# 3_Motor_Drives.net
KiCad netlist of a schematic drawn in Altium Designer
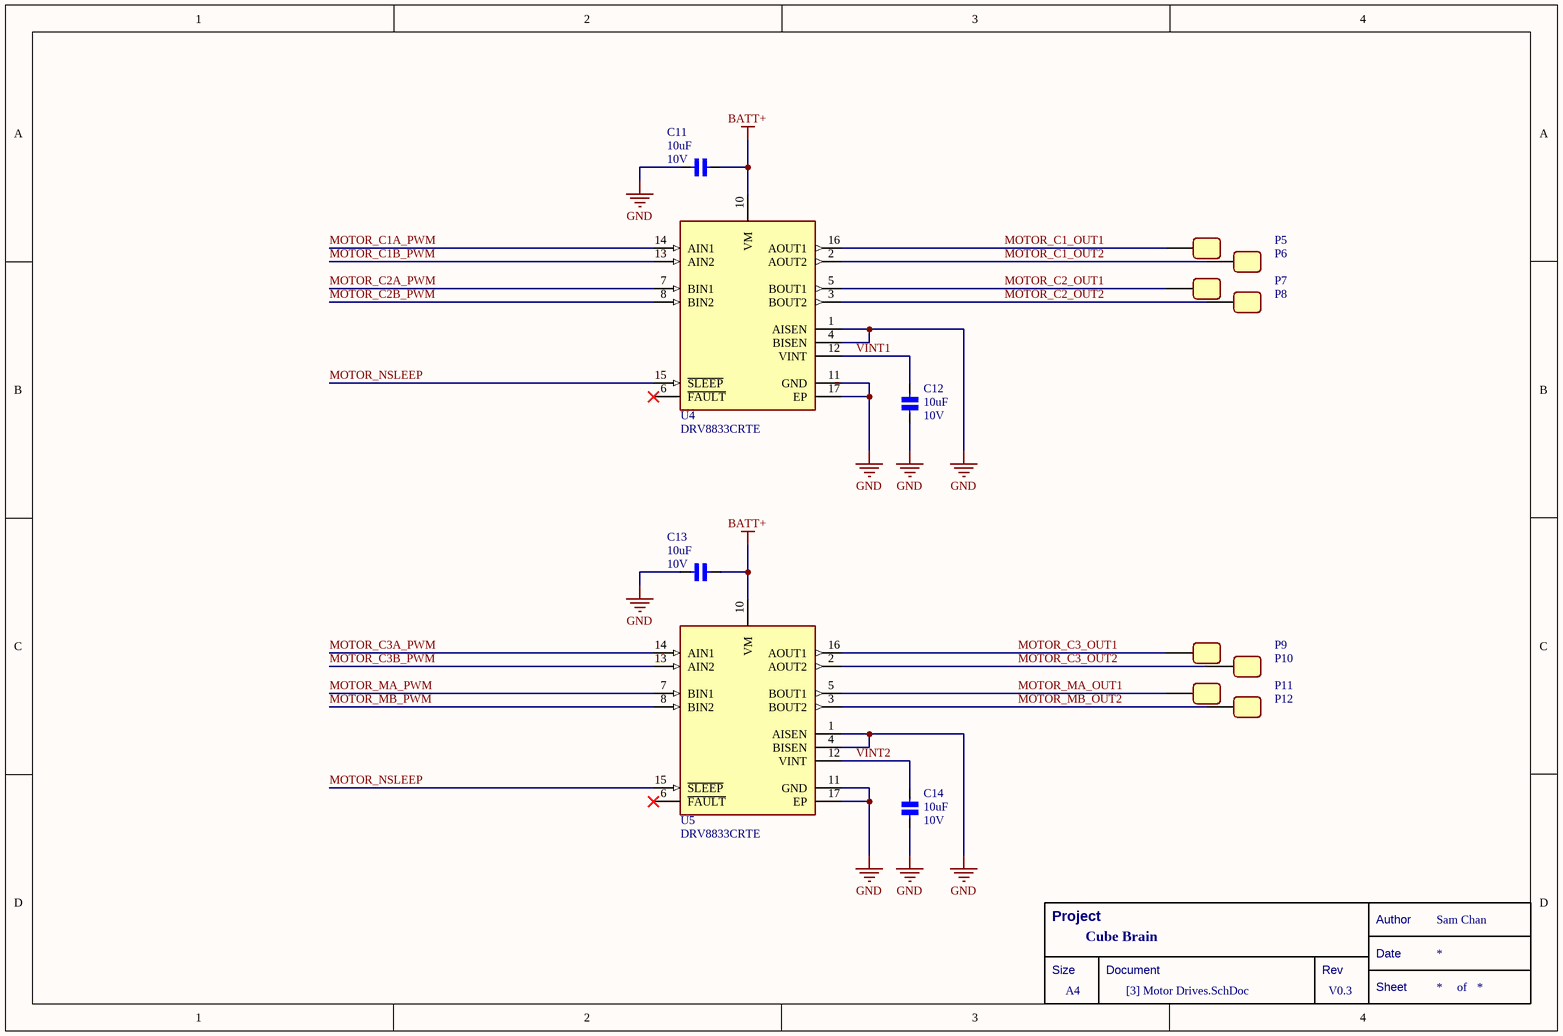
[diagram p0: [3] Motor Drives.SchDoc]

(export (version "E")
  (design (tool "Eeschema 10.0.6"))
  (components
    (comp (ref "C11")
      (value "10uF")
      (footprint "CAPC0402X05N")
      (description "CAP CER 10UF 10V X5R 0402")
      (fields
        (field (name "MANUFACTURER") "Murata Electronics")
        (field (name "MANUFACTURER PART NUMBER") "GRM155R61A106ME44D")
        (field (name "CAPACITANCE") "10uF")
        (field (name "VOLTAGE - RATED") "10V")
      )
      (libsource (lib "") (part "CER 10UF 10V_1"))
    )
    (comp (ref "C12")
      (value "10uF")
      (footprint "CAPC0402X05N")
      (description "CAP CER 10UF 10V X5R 0402")
      (fields
        (field (name "MANUFACTURER") "Murata Electronics")
        (field (name "MANUFACTURER PART NUMBER") "GRM155R61A106ME44D")
        (field (name "CAPACITANCE") "10uF")
        (field (name "VOLTAGE - RATED") "10V")
      )
      (libsource (lib "Cube Library") (part "CER 10UF 10V"))
    )
    (comp (ref "C13")
      (value "10uF")
      (footprint "CAPC0402X05N")
      (description "CAP CER 10UF 10V X5R 0402")
      (fields
        (field (name "MANUFACTURER") "Murata Electronics")
        (field (name "MANUFACTURER PART NUMBER") "GRM155R61A106ME44D")
        (field (name "CAPACITANCE") "10uF")
        (field (name "VOLTAGE - RATED") "10V")
      )
      (libsource (lib "") (part "CER 10UF 10V_1"))
    )
    (comp (ref "C14")
      (value "10uF")
      (footprint "CAPC0402X05N")
      (description "CAP CER 10UF 10V X5R 0402")
      (fields
        (field (name "MANUFACTURER") "Murata Electronics")
        (field (name "MANUFACTURER PART NUMBER") "GRM155R61A106ME44D")
        (field (name "CAPACITANCE") "10uF")
        (field (name "VOLTAGE - RATED") "10V")
      )
      (libsource (lib "Cube Library") (part "CER 10UF 10V"))
    )
    (comp (ref "P5")
      (value "PAD_1")
      (footprint "PAD_1.0X1.5MM")
      (description "a Rec Pad, 1.0X1.5mm")
      (libsource (lib "Cube Library") (part "PAD_1"))
    )
    (comp (ref "P6")
      (value "PAD_1")
      (footprint "PAD_1.0X1.5MM")
      (description "a Rec Pad, 1.0X1.5mm")
      (libsource (lib "Cube Library") (part "PAD_1"))
    )
    (comp (ref "P7")
      (value "PAD_1")
      (footprint "PAD_1.0X1.5MM")
      (description "a Rec Pad, 1.0X1.5mm")
      (libsource (lib "Cube Library") (part "PAD_1"))
    )
    (comp (ref "P8")
      (value "PAD_1")
      (footprint "PAD_1.0X1.5MM")
      (description "a Rec Pad, 1.0X1.5mm")
      (libsource (lib "Cube Library") (part "PAD_1"))
    )
    (comp (ref "P9")
      (value "PAD_1")
      (footprint "PAD_1.0X1.5MM")
      (description "a Rec Pad, 1.0X1.5mm")
      (libsource (lib "Cube Library") (part "PAD_1"))
    )
    (comp (ref "P10")
      (value "PAD_1")
      (footprint "PAD_1.0X1.5MM")
      (description "a Rec Pad, 1.0X1.5mm")
      (libsource (lib "Cube Library") (part "PAD_1"))
    )
    (comp (ref "P11")
      (value "PAD_1")
      (footprint "PAD_1.0X1.5MM")
      (description "a Rec Pad, 1.0X1.5mm")
      (libsource (lib "Cube Library") (part "PAD_1"))
    )
    (comp (ref "P12")
      (value "PAD_1")
      (footprint "PAD_1.0X1.5MM")
      (description "a Rec Pad, 1.0X1.5mm")
      (libsource (lib "Cube Library") (part "PAD_1"))
    )
    (comp (ref "U4")
      (value "DRV8833CRTE")
      (footprint "DRV8833CRTER")
      (description "Bipolar Motor Driver Power MOSFET PWM 16-WQFN (3x3)")
      (fields (field (name "MANUFACTURER") "Texas Instruments"))
      (libsource (lib "Cube Library") (part "DRV8833CRTE"))
    )
    (comp (ref "U5")
      (value "DRV8833CRTE")
      (footprint "DRV8833CRTER")
      (description "Bipolar Motor Driver Power MOSFET PWM 16-WQFN (3x3)")
      (fields (field (name "MANUFACTURER") "Texas Instruments"))
      (libsource (lib "Cube Library") (part "DRV8833CRTE"))
    )
  )
  (nets
    (net (code "1") (name "/MOTOR_C1A_PWM") (class "Default")
      (node (ref "U4") (pin "14") (pinfunction "AIN1_14") (pintype "input"))
    )
    (net (code "2") (name "/MOTOR_C1B_PWM") (class "Default")
      (node (ref "U4") (pin "13") (pinfunction "AIN2_13") (pintype "input"))
    )
    (net (code "3") (name "/MOTOR_C1_OUT1") (class "Default")
      (node (ref "P5") (pin "1") (pinfunction "1_1") (pintype "passive"))
      (node (ref "U4") (pin "16") (pinfunction "AOUT1_16") (pintype "output"))
    )
    (net (code "4") (name "/MOTOR_C1_OUT2") (class "Default")
      (node (ref "P6") (pin "1") (pinfunction "1_1") (pintype "passive"))
      (node (ref "U4") (pin "2") (pinfunction "AOUT2_2") (pintype "output"))
    )
    (net (code "5") (name "/MOTOR_C2A_PWM") (class "Default")
      (node (ref "U4") (pin "7") (pinfunction "BIN1_7") (pintype "input"))
    )
    (net (code "6") (name "/MOTOR_C2B_PWM") (class "Default")
      (node (ref "U4") (pin "8") (pinfunction "BIN2_8") (pintype "input"))
    )
    (net (code "7") (name "/MOTOR_C2_OUT1") (class "Default")
      (node (ref "P7") (pin "1") (pinfunction "1_1") (pintype "passive"))
      (node (ref "U4") (pin "5") (pinfunction "BOUT1_5") (pintype "output"))
    )
    (net (code "8") (name "/MOTOR_C2_OUT2") (class "Default")
      (node (ref "P8") (pin "1") (pinfunction "1_1") (pintype "passive"))
      (node (ref "U4") (pin "3") (pinfunction "BOUT2_3") (pintype "output"))
    )
    (net (code "9") (name "/MOTOR_C3A_PWM") (class "Default")
      (node (ref "U5") (pin "14") (pinfunction "AIN1_14") (pintype "input"))
    )
    (net (code "10") (name "/MOTOR_C3B_PWM") (class "Default")
      (node (ref "U5") (pin "13") (pinfunction "AIN2_13") (pintype "input"))
    )
    (net (code "11") (name "/MOTOR_C3_OUT1") (class "Default")
      (node (ref "P9") (pin "1") (pinfunction "1_1") (pintype "passive"))
      (node (ref "U5") (pin "16") (pinfunction "AOUT1_16") (pintype "output"))
    )
    (net (code "12") (name "/MOTOR_C3_OUT2") (class "Default")
      (node (ref "P10") (pin "1") (pinfunction "1_1") (pintype "passive"))
      (node (ref "U5") (pin "2") (pinfunction "AOUT2_2") (pintype "output"))
    )
    (net (code "13") (name "/MOTOR_MA_OUT1") (class "Default")
      (node (ref "P11") (pin "1") (pinfunction "1_1") (pintype "passive"))
      (node (ref "U5") (pin "5") (pinfunction "BOUT1_5") (pintype "output"))
    )
    (net (code "14") (name "/MOTOR_MA_PWM") (class "Default")
      (node (ref "U5") (pin "7") (pinfunction "BIN1_7") (pintype "input"))
    )
    (net (code "15") (name "/MOTOR_MB_OUT2") (class "Default")
      (node (ref "P12") (pin "1") (pinfunction "1_1") (pintype "passive"))
      (node (ref "U5") (pin "3") (pinfunction "BOUT2_3") (pintype "output"))
    )
    (net (code "16") (name "/MOTOR_MB_PWM") (class "Default")
      (node (ref "U5") (pin "8") (pinfunction "BIN2_8") (pintype "input"))
    )
    (net (code "17") (name "/MOTOR_NSLEEP") (class "Default")
      (node (ref "U4") (pin "15") (pinfunction "~{SLEEP}_15") (pintype "input"))
      (node (ref "U5") (pin "15") (pinfunction "~{SLEEP}_15") (pintype "input"))
    )
    (net (code "18") (name "/VINT1") (class "Default")
      (node (ref "C12") (pin "1") (pinfunction "1_1") (pintype "passive"))
      (node (ref "U4") (pin "12") (pinfunction "VINT_12") (pintype "power_in"))
    )
    (net (code "19") (name "/VINT2") (class "Default")
      (node (ref "C14") (pin "1") (pinfunction "1_1") (pintype "passive"))
      (node (ref "U5") (pin "12") (pinfunction "VINT_12") (pintype "power_in"))
    )
    (net (code "20") (name "BATT+") (class "Default")
      (node (ref "C11") (pin "2") (pinfunction "2_2") (pintype "passive"))
      (node (ref "C13") (pin "2") (pinfunction "2_2") (pintype "passive"))
      (node (ref "U4") (pin "10") (pinfunction "VM_10") (pintype "power_in"))
      (node (ref "U5") (pin "10") (pinfunction "VM_10") (pintype "power_in"))
    )
    (net (code "21") (name "GND") (class "Default")
      (node (ref "C11") (pin "1") (pinfunction "1_1") (pintype "passive"))
      (node (ref "C12") (pin "2") (pinfunction "2_2") (pintype "passive"))
      (node (ref "C13") (pin "1") (pinfunction "1_1") (pintype "passive"))
      (node (ref "C14") (pin "2") (pinfunction "2_2") (pintype "passive"))
      (node (ref "U4") (pin "1") (pinfunction "AISEN_1") (pintype "passive"))
      (node (ref "U4") (pin "11") (pinfunction "GND_11") (pintype "power_in"))
      (node (ref "U4") (pin "17") (pinfunction "EP_17") (pintype "passive"))
      (node (ref "U4") (pin "4") (pinfunction "BISEN_4") (pintype "passive"))
      (node (ref "U5") (pin "1") (pinfunction "AISEN_1") (pintype "passive"))
      (node (ref "U5") (pin "11") (pinfunction "GND_11") (pintype "power_in"))
      (node (ref "U5") (pin "17") (pinfunction "EP_17") (pintype "passive"))
      (node (ref "U5") (pin "4") (pinfunction "BISEN_4") (pintype "passive"))
    )
    (net (code "22") (name "unconnected-(U4-~{FAULT}-Pad6)") (class "Default")
      (node (ref "U4") (pin "6") (pinfunction "~{FAULT}_6") (pintype "open_collector+no_connect"))
    )
    (net (code "23") (name "unconnected-(U5-~{FAULT}-Pad6)") (class "Default")
      (node (ref "U5") (pin "6") (pinfunction "~{FAULT}_6") (pintype "open_collector+no_connect"))
    )
  )
)
